# schematic.net
KiCad netlist of a schematic drawn in EasyEDA
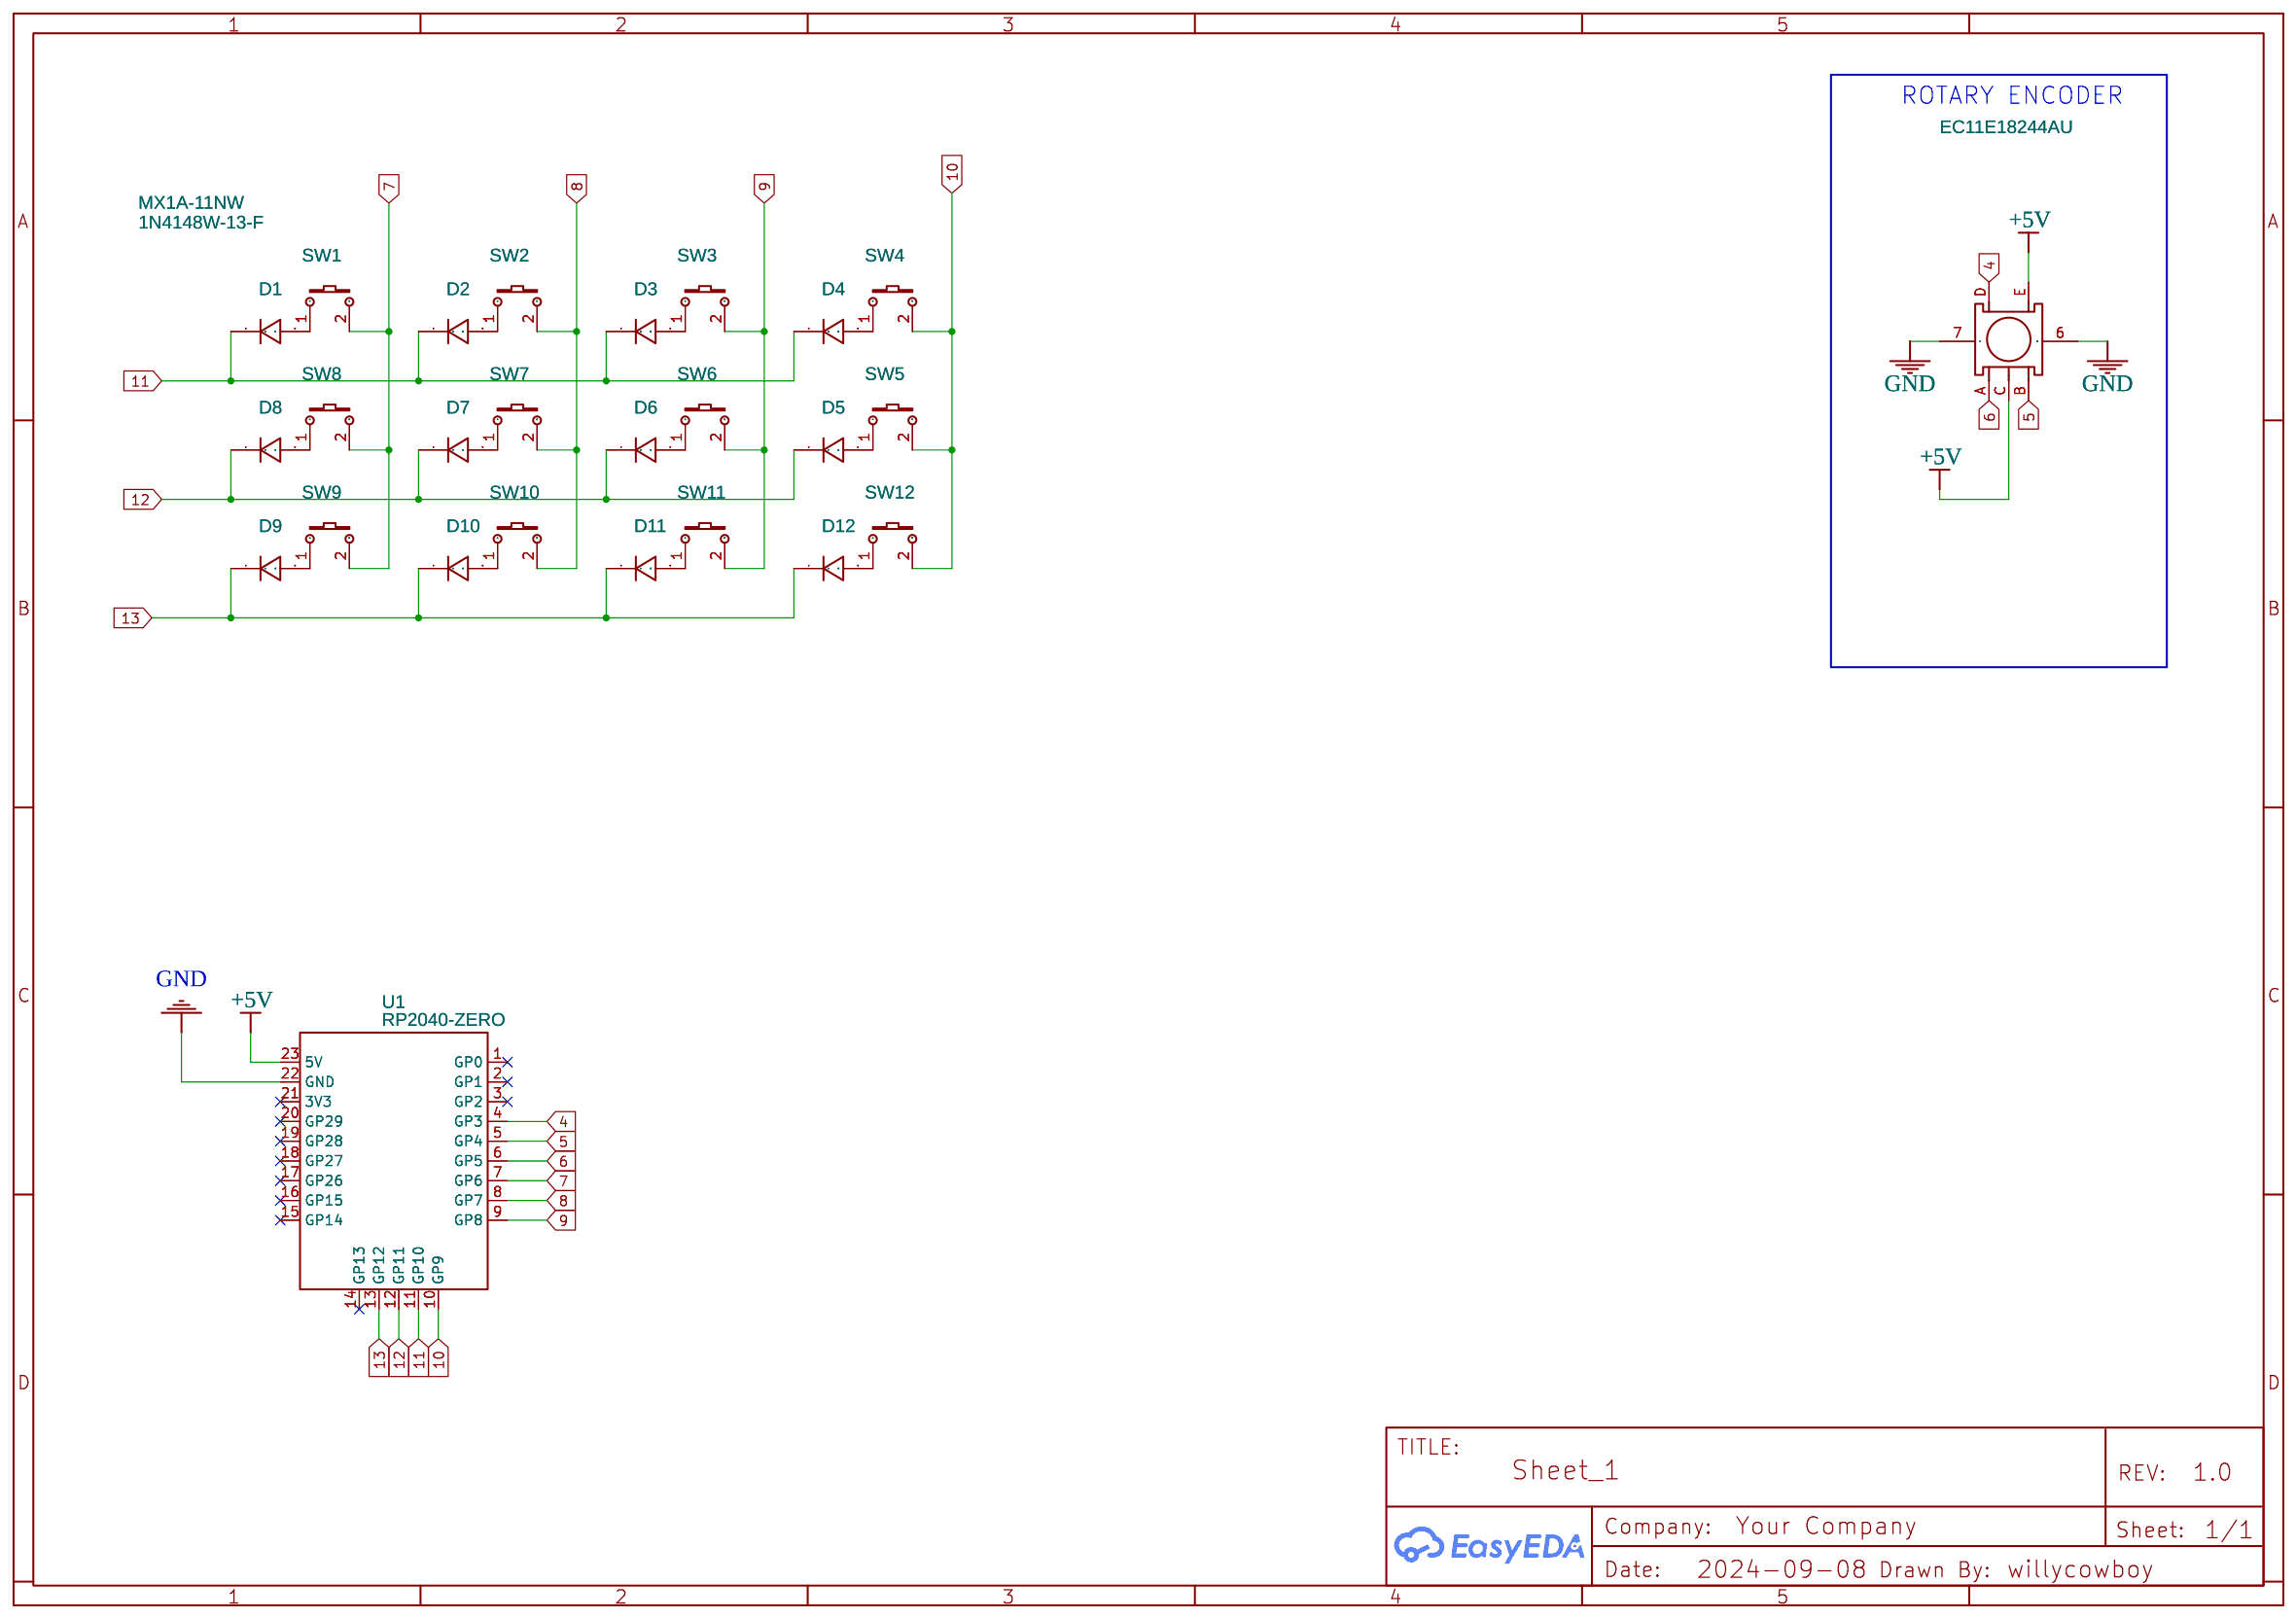
[diagram p0: schematic sheet]

(export (version "E")
  (design (tool "Eeschema 10.0.6"))
  (components
    (comp (ref "D1")
      (value "1N4148W-13-F")
      (fields (field (name "Manufacturer") "DIODES(美台)"))
      (libsource (lib "") (part "1N4148W-13-F"))
    )
    (comp (ref "D2")
      (value "1N4148W-13-F")
      (fields (field (name "Manufacturer") "DIODES(美台)"))
      (libsource (lib "") (part "1N4148W-13-F"))
    )
    (comp (ref "D3")
      (value "1N4148W-13-F")
      (fields (field (name "Manufacturer") "DIODES(美台)"))
      (libsource (lib "") (part "1N4148W-13-F"))
    )
    (comp (ref "D4")
      (value "1N4148W-13-F")
      (fields (field (name "Manufacturer") "DIODES(美台)"))
      (libsource (lib "") (part "1N4148W-13-F"))
    )
    (comp (ref "D5")
      (value "1N4148W-13-F")
      (fields (field (name "Manufacturer") "DIODES(美台)"))
      (libsource (lib "") (part "1N4148W-13-F"))
    )
    (comp (ref "D6")
      (value "1N4148W-13-F")
      (fields (field (name "Manufacturer") "DIODES(美台)"))
      (libsource (lib "") (part "1N4148W-13-F"))
    )
    (comp (ref "D7")
      (value "1N4148W-13-F")
      (fields (field (name "Manufacturer") "DIODES(美台)"))
      (libsource (lib "") (part "1N4148W-13-F"))
    )
    (comp (ref "D8")
      (value "1N4148W-13-F")
      (fields (field (name "Manufacturer") "DIODES(美台)"))
      (libsource (lib "") (part "1N4148W-13-F"))
    )
    (comp (ref "D9")
      (value "1N4148W-13-F")
      (fields (field (name "Manufacturer") "DIODES(美台)"))
      (libsource (lib "") (part "1N4148W-13-F"))
    )
    (comp (ref "D10")
      (value "1N4148W-13-F")
      (fields (field (name "Manufacturer") "DIODES(美台)"))
      (libsource (lib "") (part "1N4148W-13-F"))
    )
    (comp (ref "D11")
      (value "1N4148W-13-F")
      (fields (field (name "Manufacturer") "DIODES(美台)"))
      (libsource (lib "") (part "1N4148W-13-F"))
    )
    (comp (ref "D12")
      (value "1N4148W-13-F")
      (fields (field (name "Manufacturer") "DIODES(美台)"))
      (libsource (lib "") (part "1N4148W-13-F"))
    )
    (comp (ref "SW1")
      (value "MX1A-11NW")
      (fields (field (name "Manufacturer") "CHERRY"))
      (libsource (lib "") (part "MX1A-11NW"))
    )
    (comp (ref "SW2")
      (value "MX1A-11NW")
      (fields (field (name "Manufacturer") "CHERRY"))
      (libsource (lib "") (part "MX1A-11NW"))
    )
    (comp (ref "SW3")
      (value "MX1A-11NW")
      (fields (field (name "Manufacturer") "CHERRY"))
      (libsource (lib "") (part "MX1A-11NW"))
    )
    (comp (ref "SW4")
      (value "MX1A-11NW")
      (fields (field (name "Manufacturer") "CHERRY"))
      (libsource (lib "") (part "MX1A-11NW"))
    )
    (comp (ref "SW5")
      (value "MX1A-11NW")
      (fields (field (name "Manufacturer") "CHERRY"))
      (libsource (lib "") (part "MX1A-11NW"))
    )
    (comp (ref "SW6")
      (value "MX1A-11NW")
      (fields (field (name "Manufacturer") "CHERRY"))
      (libsource (lib "") (part "MX1A-11NW"))
    )
    (comp (ref "SW7")
      (value "MX1A-11NW")
      (fields (field (name "Manufacturer") "CHERRY"))
      (libsource (lib "") (part "MX1A-11NW"))
    )
    (comp (ref "SW8")
      (value "MX1A-11NW")
      (fields (field (name "Manufacturer") "CHERRY"))
      (libsource (lib "") (part "MX1A-11NW"))
    )
    (comp (ref "SW9")
      (value "MX1A-11NW")
      (fields (field (name "Manufacturer") "CHERRY"))
      (libsource (lib "") (part "MX1A-11NW"))
    )
    (comp (ref "SW10")
      (value "MX1A-11NW")
      (fields (field (name "Manufacturer") "CHERRY"))
      (libsource (lib "") (part "MX1A-11NW"))
    )
    (comp (ref "SW11")
      (value "MX1A-11NW")
      (fields (field (name "Manufacturer") "CHERRY"))
      (libsource (lib "") (part "MX1A-11NW"))
    )
    (comp (ref "SW12")
      (value "MX1A-11NW")
      (fields (field (name "Manufacturer") "CHERRY"))
      (libsource (lib "") (part "MX1A-11NW"))
    )
    (comp (ref "SW13")
      (value "EC11E18244AU")
      (fields (field (name "Manufacturer") "ALPSALPINE(阿尔卑斯阿尔派)"))
      (libsource (lib "") (part "EC11E18244AU"))
    )
    (comp (ref "U1")
      (value "RP2040-ZERO")
      (fields
        (field (name "Manufacturer Part") "RP2040-Zero")
        (field (name "Manufacturer") "Waveshare(微雪电子)")
      )
      (libsource (lib "") (part "RP2040-ZERO"))
    )
  )
  (nets
    (net (code "1") (name "+5V") (class "Default")
      (node (ref "SW13") (pin "C") (pinfunction "C_C") (pintype "unspecified"))
      (node (ref "SW13") (pin "E") (pinfunction "E_E") (pintype "unspecified"))
      (node (ref "U1") (pin "23") (pinfunction "5V_23") (pintype "unspecified"))
    )
    (net (code "2") (name "4") (class "Default")
      (node (ref "SW13") (pin "D") (pinfunction "D_D") (pintype "unspecified"))
      (node (ref "U1") (pin "4") (pinfunction "GP3_4") (pintype "unspecified"))
    )
    (net (code "3") (name "5") (class "Default")
      (node (ref "SW13") (pin "B") (pinfunction "B_B") (pintype "unspecified"))
      (node (ref "U1") (pin "5") (pinfunction "GP4_5") (pintype "unspecified"))
    )
    (net (code "4") (name "6") (class "Default")
      (node (ref "SW13") (pin "A") (pinfunction "A_A") (pintype "unspecified"))
      (node (ref "U1") (pin "6") (pinfunction "GP5_6") (pintype "unspecified"))
    )
    (net (code "5") (name "7") (class "Default")
      (node (ref "SW1") (pin "2") (pinfunction "2_2") (pintype "unspecified"))
      (node (ref "SW8") (pin "2") (pinfunction "2_2") (pintype "unspecified"))
      (node (ref "SW9") (pin "2") (pinfunction "2_2") (pintype "unspecified"))
      (node (ref "U1") (pin "7") (pinfunction "GP6_7") (pintype "unspecified"))
    )
    (net (code "6") (name "8") (class "Default")
      (node (ref "SW10") (pin "2") (pinfunction "2_2") (pintype "unspecified"))
      (node (ref "SW2") (pin "2") (pinfunction "2_2") (pintype "unspecified"))
      (node (ref "SW7") (pin "2") (pinfunction "2_2") (pintype "unspecified"))
      (node (ref "U1") (pin "8") (pinfunction "GP7_8") (pintype "unspecified"))
    )
    (net (code "7") (name "9") (class "Default")
      (node (ref "SW11") (pin "2") (pinfunction "2_2") (pintype "unspecified"))
      (node (ref "SW3") (pin "2") (pinfunction "2_2") (pintype "unspecified"))
      (node (ref "SW6") (pin "2") (pinfunction "2_2") (pintype "unspecified"))
      (node (ref "U1") (pin "9") (pinfunction "GP8_9") (pintype "unspecified"))
    )
    (net (code "8") (name "10") (class "Default")
      (node (ref "SW12") (pin "2") (pinfunction "2_2") (pintype "unspecified"))
      (node (ref "SW4") (pin "2") (pinfunction "2_2") (pintype "unspecified"))
      (node (ref "SW5") (pin "2") (pinfunction "2_2") (pintype "unspecified"))
      (node (ref "U1") (pin "10") (pinfunction "GP9_10") (pintype "unspecified"))
    )
    (net (code "9") (name "11") (class "Default")
      (node (ref "D1") (pin "1") (pinfunction "1_1") (pintype "unspecified"))
      (node (ref "D2") (pin "1") (pinfunction "1_1") (pintype "unspecified"))
      (node (ref "D3") (pin "1") (pinfunction "1_1") (pintype "unspecified"))
      (node (ref "D4") (pin "1") (pinfunction "1_1") (pintype "unspecified"))
      (node (ref "U1") (pin "11") (pinfunction "GP10_11") (pintype "unspecified"))
    )
    (net (code "10") (name "12") (class "Default")
      (node (ref "D5") (pin "1") (pinfunction "1_1") (pintype "unspecified"))
      (node (ref "D6") (pin "1") (pinfunction "1_1") (pintype "unspecified"))
      (node (ref "D7") (pin "1") (pinfunction "1_1") (pintype "unspecified"))
      (node (ref "D8") (pin "1") (pinfunction "1_1") (pintype "unspecified"))
      (node (ref "U1") (pin "12") (pinfunction "GP11_12") (pintype "unspecified"))
    )
    (net (code "11") (name "13") (class "Default")
      (node (ref "D10") (pin "1") (pinfunction "1_1") (pintype "unspecified"))
      (node (ref "D11") (pin "1") (pinfunction "1_1") (pintype "unspecified"))
      (node (ref "D12") (pin "1") (pinfunction "1_1") (pintype "unspecified"))
      (node (ref "D9") (pin "1") (pinfunction "1_1") (pintype "unspecified"))
      (node (ref "U1") (pin "13") (pinfunction "GP12_13") (pintype "unspecified"))
    )
    (net (code "12") (name "GND") (class "Default")
      (node (ref "SW13") (pin "6") (pinfunction "6_6") (pintype "unspecified"))
      (node (ref "SW13") (pin "7") (pinfunction "7_7") (pintype "unspecified"))
      (node (ref "U1") (pin "22") (pinfunction "GND_22") (pintype "unspecified"))
    )
    (net (code "13") (name "Net-(D1-Pad2)") (class "Default")
      (node (ref "D1") (pin "2") (pinfunction "2_2") (pintype "unspecified"))
      (node (ref "SW1") (pin "1") (pinfunction "1_1") (pintype "unspecified"))
    )
    (net (code "14") (name "Net-(D2-Pad2)") (class "Default")
      (node (ref "D2") (pin "2") (pinfunction "2_2") (pintype "unspecified"))
      (node (ref "SW2") (pin "1") (pinfunction "1_1") (pintype "unspecified"))
    )
    (net (code "15") (name "Net-(D3-Pad2)") (class "Default")
      (node (ref "D3") (pin "2") (pinfunction "2_2") (pintype "unspecified"))
      (node (ref "SW3") (pin "1") (pinfunction "1_1") (pintype "unspecified"))
    )
    (net (code "16") (name "Net-(D4-Pad2)") (class "Default")
      (node (ref "D4") (pin "2") (pinfunction "2_2") (pintype "unspecified"))
      (node (ref "SW4") (pin "1") (pinfunction "1_1") (pintype "unspecified"))
    )
    (net (code "17") (name "Net-(D5-Pad2)") (class "Default")
      (node (ref "D5") (pin "2") (pinfunction "2_2") (pintype "unspecified"))
      (node (ref "SW5") (pin "1") (pinfunction "1_1") (pintype "unspecified"))
    )
    (net (code "18") (name "Net-(D6-Pad2)") (class "Default")
      (node (ref "D6") (pin "2") (pinfunction "2_2") (pintype "unspecified"))
      (node (ref "SW6") (pin "1") (pinfunction "1_1") (pintype "unspecified"))
    )
    (net (code "19") (name "Net-(D7-Pad2)") (class "Default")
      (node (ref "D7") (pin "2") (pinfunction "2_2") (pintype "unspecified"))
      (node (ref "SW7") (pin "1") (pinfunction "1_1") (pintype "unspecified"))
    )
    (net (code "20") (name "Net-(D8-Pad2)") (class "Default")
      (node (ref "D8") (pin "2") (pinfunction "2_2") (pintype "unspecified"))
      (node (ref "SW8") (pin "1") (pinfunction "1_1") (pintype "unspecified"))
    )
    (net (code "21") (name "Net-(D9-Pad2)") (class "Default")
      (node (ref "D9") (pin "2") (pinfunction "2_2") (pintype "unspecified"))
      (node (ref "SW9") (pin "1") (pinfunction "1_1") (pintype "unspecified"))
    )
    (net (code "22") (name "Net-(D10-Pad2)") (class "Default")
      (node (ref "D10") (pin "2") (pinfunction "2_2") (pintype "unspecified"))
      (node (ref "SW10") (pin "1") (pinfunction "1_1") (pintype "unspecified"))
    )
    (net (code "23") (name "Net-(D11-Pad2)") (class "Default")
      (node (ref "D11") (pin "2") (pinfunction "2_2") (pintype "unspecified"))
      (node (ref "SW11") (pin "1") (pinfunction "1_1") (pintype "unspecified"))
    )
    (net (code "24") (name "Net-(D12-Pad2)") (class "Default")
      (node (ref "D12") (pin "2") (pinfunction "2_2") (pintype "unspecified"))
      (node (ref "SW12") (pin "1") (pinfunction "1_1") (pintype "unspecified"))
    )
    (net (code "25") (name "unconnected-(U1-3V3-Pad21)") (class "Default")
      (node (ref "U1") (pin "21") (pinfunction "3V3_21") (pintype "unspecified+no_connect"))
    )
    (net (code "26") (name "unconnected-(U1-GP0-Pad1)") (class "Default")
      (node (ref "U1") (pin "1") (pinfunction "GP0_1") (pintype "unspecified+no_connect"))
    )
    (net (code "27") (name "unconnected-(U1-GP1-Pad2)") (class "Default")
      (node (ref "U1") (pin "2") (pinfunction "GP1_2") (pintype "unspecified+no_connect"))
    )
    (net (code "28") (name "unconnected-(U1-GP2-Pad3)") (class "Default")
      (node (ref "U1") (pin "3") (pinfunction "GP2_3") (pintype "unspecified+no_connect"))
    )
    (net (code "29") (name "unconnected-(U1-GP13-Pad14)") (class "Default")
      (node (ref "U1") (pin "14") (pinfunction "GP13_14") (pintype "unspecified+no_connect"))
    )
    (net (code "30") (name "unconnected-(U1-GP14-Pad15)") (class "Default")
      (node (ref "U1") (pin "15") (pinfunction "GP14_15") (pintype "unspecified+no_connect"))
    )
    (net (code "31") (name "unconnected-(U1-GP15-Pad16)") (class "Default")
      (node (ref "U1") (pin "16") (pinfunction "GP15_16") (pintype "unspecified+no_connect"))
    )
    (net (code "32") (name "unconnected-(U1-GP26-Pad17)") (class "Default")
      (node (ref "U1") (pin "17") (pinfunction "GP26_17") (pintype "unspecified+no_connect"))
    )
    (net (code "33") (name "unconnected-(U1-GP27-Pad18)") (class "Default")
      (node (ref "U1") (pin "18") (pinfunction "GP27_18") (pintype "unspecified+no_connect"))
    )
    (net (code "34") (name "unconnected-(U1-GP28-Pad19)") (class "Default")
      (node (ref "U1") (pin "19") (pinfunction "GP28_19") (pintype "unspecified+no_connect"))
    )
    (net (code "35") (name "unconnected-(U1-GP29-Pad20)") (class "Default")
      (node (ref "U1") (pin "20") (pinfunction "GP29_20") (pintype "unspecified+no_connect"))
    )
  )
)
